# Mainboard.net
KiCad netlist of a schematic drawn in EAGLE
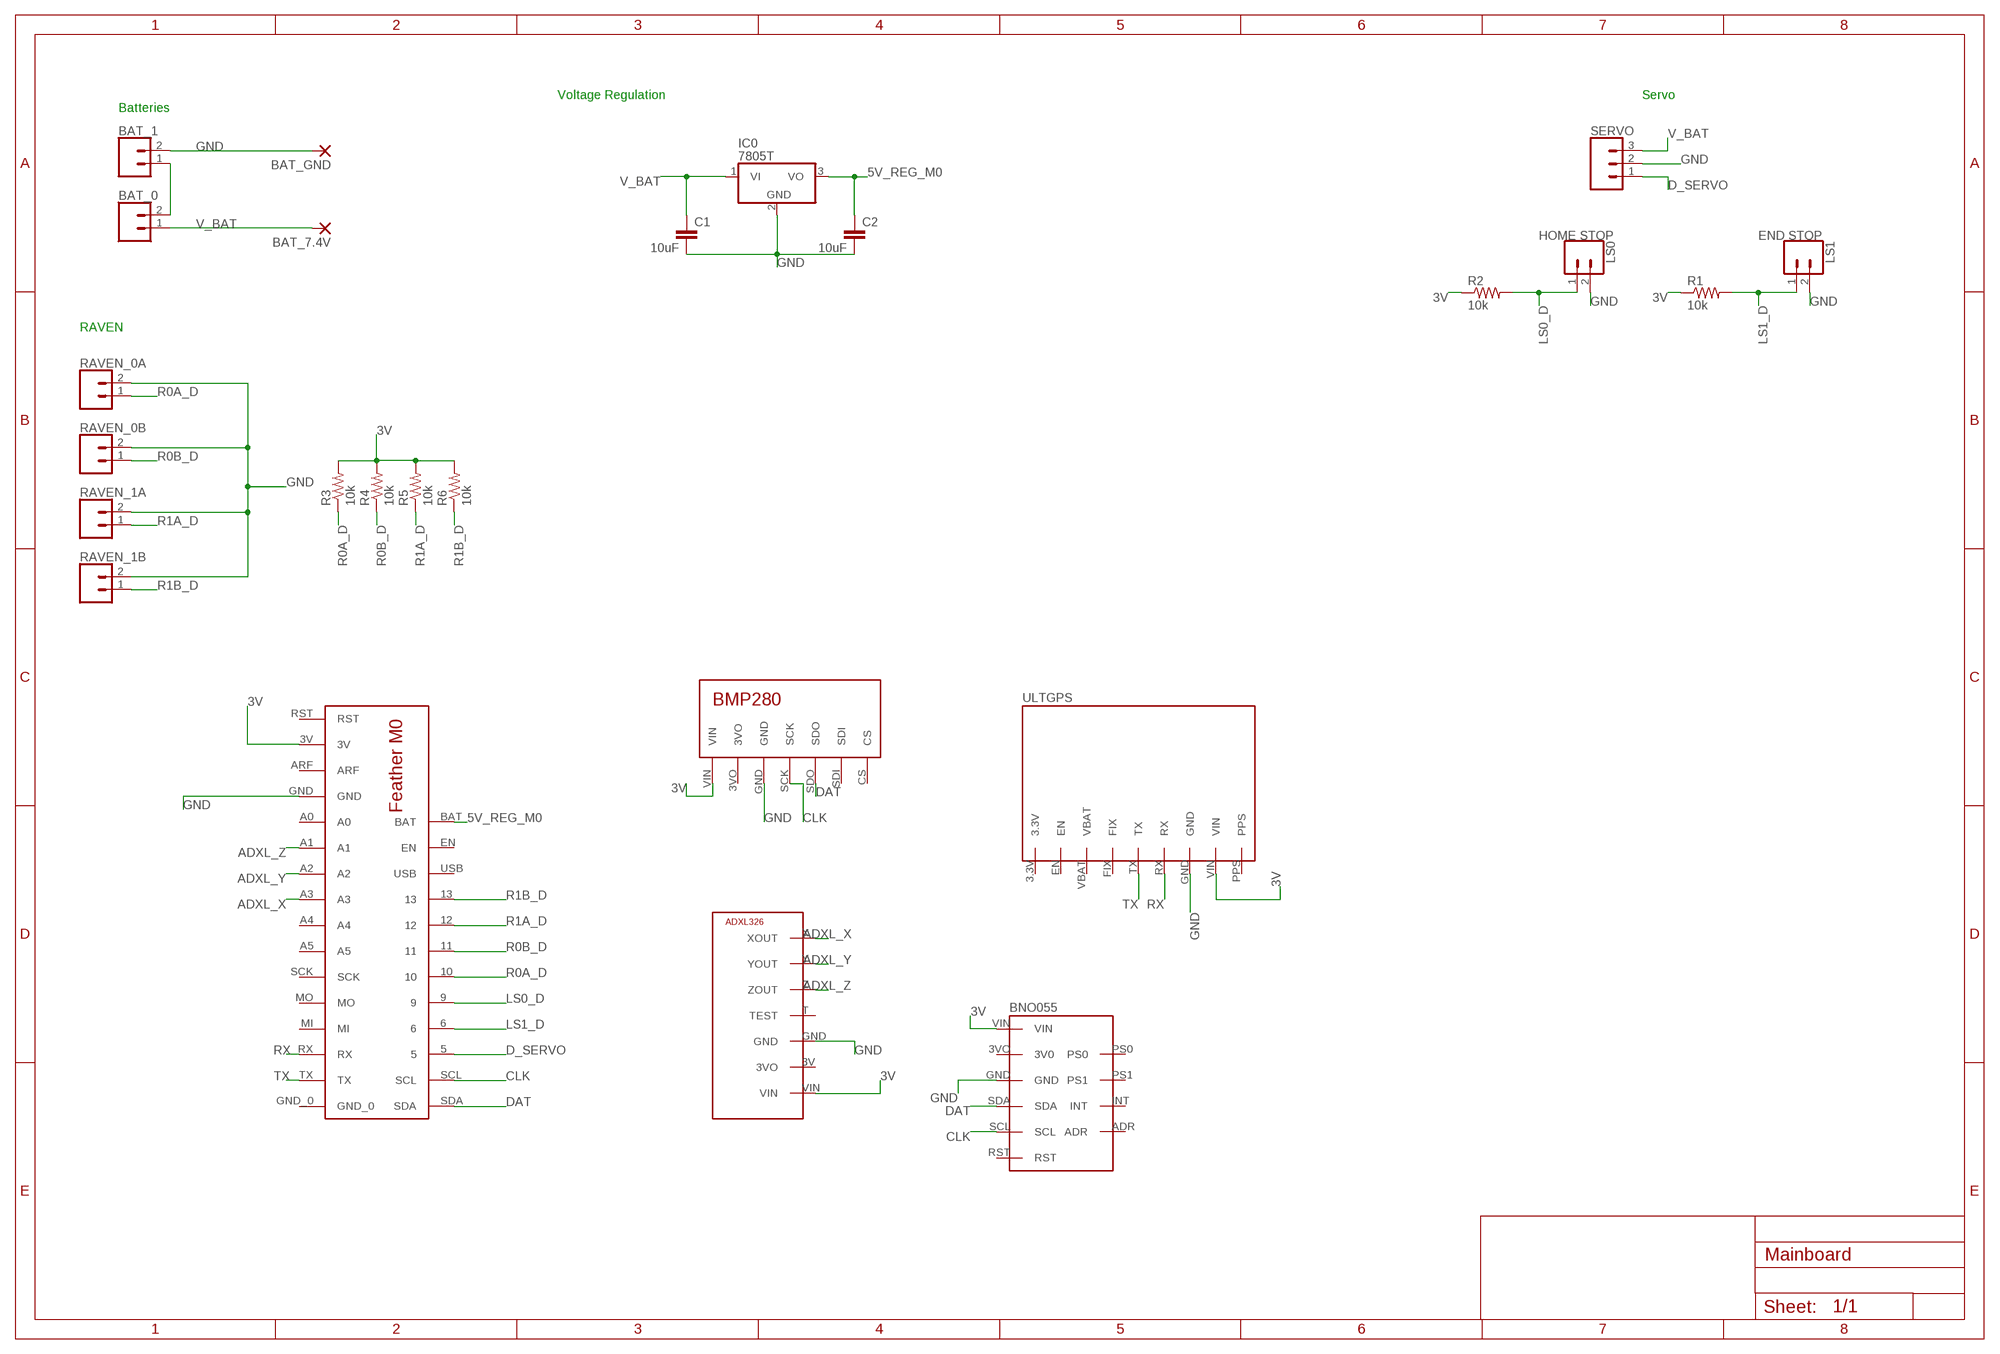
[diagram p0: schematic, sheet 1]

(export (version "E")
  (design (tool "Eeschema 10.0.6"))
  (components
    (comp (ref "BAT_0")
      (value "CONN_02JST-PTH-2")
      (footprint "eagle-import:JST-2-PTH")
      (libsource (lib "eagle-import") (part "CONN_02JST-PTH-2"))
    )
    (comp (ref "BAT_1")
      (value "CONN_02JST-PTH-2")
      (footprint "eagle-import:JST-2-PTH")
      (libsource (lib "eagle-import") (part "CONN_02JST-PTH-2"))
    )
    (comp (ref "BAT_7.4V")
      (value "3,81/1,4")
      (footprint "eagle-import:3,81_1,4")
      (libsource (lib "eagle-import") (part "3,81/1,4"))
    )
    (comp (ref "BAT_GND")
      (value "3,81/1,4")
      (footprint "eagle-import:3,81_1,4")
      (libsource (lib "eagle-import") (part "3,81/1,4"))
    )
    (comp (ref "C1")
      (value "10uF")
      (footprint "eagle-import:C2.5-3")
      (libsource (lib "eagle-import") (part "C2,5-3"))
    )
    (comp (ref "C2")
      (value "10uF")
      (footprint "eagle-import:C2.5-3")
      (libsource (lib "eagle-import") (part "C2,5-3"))
    )
    (comp (ref "IC0")
      (value "7805T")
      (footprint "eagle-import:TO220H")
      (libsource (lib "eagle-import") (part "78T05"))
    )
    (comp (ref "LS0")
      (value "HOME STOP")
      (footprint "eagle-import:JST-2-PTH")
      (libsource (lib "eagle-import") (part "CONN_02JST-PTH-2"))
    )
    (comp (ref "LS1")
      (value "END STOP")
      (footprint "eagle-import:JST-2-PTH")
      (libsource (lib "eagle-import") (part "CONN_02JST-PTH-2"))
    )
    (comp (ref "R1")
      (value "10k")
      (footprint "eagle-import:0207_10")
      (libsource (lib "eagle-import") (part "R-US_0207/10"))
    )
    (comp (ref "R2")
      (value "10k")
      (footprint "eagle-import:0207_10")
      (libsource (lib "eagle-import") (part "R-US_0207/10"))
    )
    (comp (ref "R3")
      (value "10k")
      (footprint "eagle-import:0207_10")
      (libsource (lib "eagle-import") (part "R-US_0207/10"))
    )
    (comp (ref "R4")
      (value "10k")
      (footprint "eagle-import:0207_10")
      (libsource (lib "eagle-import") (part "R-US_0207/10"))
    )
    (comp (ref "R5")
      (value "10k")
      (footprint "eagle-import:0207_10")
      (libsource (lib "eagle-import") (part "R-US_0207/10"))
    )
    (comp (ref "R6")
      (value "10k")
      (footprint "eagle-import:0207_10")
      (libsource (lib "eagle-import") (part "R-US_0207/10"))
    )
    (comp (ref "RAVEN_0A")
      (value "CONN_02JST-PTH-2")
      (footprint "eagle-import:JST-2-PTH")
      (libsource (lib "eagle-import") (part "CONN_02JST-PTH-2"))
    )
    (comp (ref "RAVEN_0B")
      (value "CONN_02JST-PTH-2")
      (footprint "eagle-import:JST-2-PTH")
      (libsource (lib "eagle-import") (part "CONN_02JST-PTH-2"))
    )
    (comp (ref "RAVEN_1A")
      (value "CONN_02JST-PTH-2")
      (footprint "eagle-import:JST-2-PTH")
      (libsource (lib "eagle-import") (part "CONN_02JST-PTH-2"))
    )
    (comp (ref "RAVEN_1B")
      (value "CONN_02JST-PTH-2")
      (footprint "eagle-import:JST-2-PTH")
      (libsource (lib "eagle-import") (part "CONN_02JST-PTH-2"))
    )
    (comp (ref "SERVO")
      (value "CONN_03JST-PTH")
      (footprint "eagle-import:JST-3-PTH")
      (libsource (lib "eagle-import") (part "CONN_03JST-PTH"))
    )
    (comp (ref "U$1") (value "M0") (footprint "eagle-import:M0") (libsource (lib "eagle-import") (part "M0")))
    (comp (ref "U$2")
      (value "BMP")
      (footprint "eagle-import:BMP")
      (libsource (lib "eagle-import") (part "BMP"))
    )
    (comp (ref "U$3")
      (value "ADXL377")
      (footprint "eagle-import:ADXL377")
      (libsource (lib "eagle-import") (part "ADXL377"))
    )
    (comp (ref "U$4")
      (value "ULTGPS")
      (footprint "eagle-import:ULTGPS")
      (libsource (lib "eagle-import") (part "ULTGPS"))
    )
    (comp (ref "U$5")
      (value "BNO055")
      (footprint "eagle-import:BNO055")
      (libsource (lib "eagle-import") (part "BNO055"))
    )
  )
  (nets
    (net (code "1") (name "/3V") (class "Default")
      (node (ref "R1") (pin "1") (pinfunction "1_1") (pintype "passive"))
      (node (ref "R2") (pin "1") (pinfunction "1_1") (pintype "passive"))
      (node (ref "R3") (pin "2") (pinfunction "2_2") (pintype "passive"))
      (node (ref "R4") (pin "2") (pinfunction "2_2") (pintype "passive"))
      (node (ref "R5") (pin "2") (pinfunction "2_2") (pintype "passive"))
      (node (ref "R6") (pin "2") (pinfunction "2_2") (pintype "passive"))
      (node (ref "U$1") (pin "3V") (pinfunction "3V_3V") (pintype "bidirectional"))
      (node (ref "U$2") (pin "VIN") (pinfunction "VIN_VIN") (pintype "bidirectional"))
      (node (ref "U$3") (pin "VIN") (pinfunction "VIN_VIN") (pintype "bidirectional"))
      (node (ref "U$4") (pin "VIN") (pinfunction "VIN_VIN") (pintype "input"))
      (node (ref "U$5") (pin "VIN") (pinfunction "VIN_VIN") (pintype "bidirectional"))
    )
    (net (code "2") (name "/5V_REG_M0") (class "Default")
      (node (ref "C2") (pin "1") (pinfunction "1_1") (pintype "passive"))
      (node (ref "IC0") (pin "3") (pinfunction "VO_3") (pintype "passive"))
      (node (ref "U$1") (pin "BAT") (pinfunction "BAT_BAT") (pintype "bidirectional"))
    )
    (net (code "3") (name "/ADXL_X") (class "Default")
      (node (ref "U$1") (pin "A3") (pinfunction "A3_A3") (pintype "bidirectional"))
      (node (ref "U$3") (pin "X") (pinfunction "XOUT_X") (pintype "bidirectional"))
    )
    (net (code "4") (name "/ADXL_Y") (class "Default")
      (node (ref "U$1") (pin "A2") (pinfunction "A2_A2") (pintype "bidirectional"))
      (node (ref "U$3") (pin "Y") (pinfunction "YOUT_Y") (pintype "bidirectional"))
    )
    (net (code "5") (name "/ADXL_Z") (class "Default")
      (node (ref "U$1") (pin "A1") (pinfunction "A1_A1") (pintype "bidirectional"))
      (node (ref "U$3") (pin "Z") (pinfunction "ZOUT_Z") (pintype "bidirectional"))
    )
    (net (code "6") (name "/CLK") (class "Default")
      (node (ref "U$1") (pin "SCL") (pinfunction "SCL_SCL") (pintype "bidirectional"))
      (node (ref "U$2") (pin "SCK") (pinfunction "SCK_SCK") (pintype "bidirectional"))
      (node (ref "U$5") (pin "SCL") (pinfunction "SCL_SCL") (pintype "bidirectional"))
    )
    (net (code "7") (name "/DAT") (class "Default")
      (node (ref "U$1") (pin "SDA") (pinfunction "SDA_SDA") (pintype "bidirectional"))
      (node (ref "U$2") (pin "SDO") (pinfunction "SDO_SDO") (pintype "bidirectional"))
      (node (ref "U$5") (pin "SDA") (pinfunction "SDA_SDA") (pintype "bidirectional"))
    )
    (net (code "8") (name "/D_SERVO") (class "Default")
      (node (ref "SERVO") (pin "1") (pinfunction "1_1") (pintype "passive"))
      (node (ref "U$1") (pin "5") (pinfunction "5_5") (pintype "bidirectional"))
    )
    (net (code "9") (name "/GND") (class "Default")
      (node (ref "BAT_1") (pin "2") (pinfunction "2_2") (pintype "passive"))
      (node (ref "BAT_GND") (pin "1") (pinfunction "P_1") (pintype "passive"))
      (node (ref "C1") (pin "2") (pinfunction "2_2") (pintype "passive"))
      (node (ref "C2") (pin "2") (pinfunction "2_2") (pintype "passive"))
      (node (ref "IC0") (pin "2") (pinfunction "GND_2") (pintype "passive"))
      (node (ref "LS0") (pin "2") (pinfunction "2_2") (pintype "passive"))
      (node (ref "LS1") (pin "2") (pinfunction "2_2") (pintype "passive"))
      (node (ref "RAVEN_0A") (pin "2") (pinfunction "2_2") (pintype "passive"))
      (node (ref "RAVEN_0B") (pin "2") (pinfunction "2_2") (pintype "passive"))
      (node (ref "RAVEN_1A") (pin "2") (pinfunction "2_2") (pintype "passive"))
      (node (ref "RAVEN_1B") (pin "2") (pinfunction "2_2") (pintype "passive"))
      (node (ref "SERVO") (pin "2") (pinfunction "2_2") (pintype "passive"))
      (node (ref "U$1") (pin "GND") (pinfunction "GND_GND") (pintype "bidirectional"))
      (node (ref "U$2") (pin "GND") (pinfunction "GND_GND") (pintype "bidirectional"))
      (node (ref "U$3") (pin "GND") (pinfunction "GND_GND") (pintype "bidirectional"))
      (node (ref "U$4") (pin "GND") (pinfunction "GND_GND") (pintype "power_in"))
      (node (ref "U$5") (pin "GND") (pinfunction "GND_GND") (pintype "bidirectional"))
    )
    (net (code "10") (name "/LS0_D") (class "Default")
      (node (ref "LS0") (pin "1") (pinfunction "1_1") (pintype "passive"))
      (node (ref "R2") (pin "2") (pinfunction "2_2") (pintype "passive"))
      (node (ref "U$1") (pin "9") (pinfunction "9_9") (pintype "bidirectional"))
    )
    (net (code "11") (name "/LS1_D") (class "Default")
      (node (ref "LS1") (pin "1") (pinfunction "1_1") (pintype "passive"))
      (node (ref "R1") (pin "2") (pinfunction "2_2") (pintype "passive"))
      (node (ref "U$1") (pin "6") (pinfunction "6_6") (pintype "bidirectional"))
    )
    (net (code "12") (name "/R0A_D") (class "Default")
      (node (ref "R3") (pin "1") (pinfunction "1_1") (pintype "passive"))
      (node (ref "RAVEN_0A") (pin "1") (pinfunction "1_1") (pintype "passive"))
      (node (ref "U$1") (pin "10") (pinfunction "10_10") (pintype "bidirectional"))
    )
    (net (code "13") (name "/R0B_D") (class "Default")
      (node (ref "R4") (pin "1") (pinfunction "1_1") (pintype "passive"))
      (node (ref "RAVEN_0B") (pin "1") (pinfunction "1_1") (pintype "passive"))
      (node (ref "U$1") (pin "11") (pinfunction "11_11") (pintype "bidirectional"))
    )
    (net (code "14") (name "/R1A_D") (class "Default")
      (node (ref "R5") (pin "1") (pinfunction "1_1") (pintype "passive"))
      (node (ref "RAVEN_1A") (pin "1") (pinfunction "1_1") (pintype "passive"))
      (node (ref "U$1") (pin "12") (pinfunction "12_12") (pintype "bidirectional"))
    )
    (net (code "15") (name "/R1B_D") (class "Default")
      (node (ref "R6") (pin "1") (pinfunction "1_1") (pintype "passive"))
      (node (ref "RAVEN_1B") (pin "1") (pinfunction "1_1") (pintype "passive"))
      (node (ref "U$1") (pin "13") (pinfunction "13_13") (pintype "bidirectional"))
    )
    (net (code "16") (name "/RX") (class "Default")
      (node (ref "U$1") (pin "RX") (pinfunction "RX_RX") (pintype "bidirectional"))
      (node (ref "U$4") (pin "RX") (pinfunction "RX_RX") (pintype "input"))
    )
    (net (code "17") (name "/TX") (class "Default")
      (node (ref "U$1") (pin "TX") (pinfunction "TX_TX") (pintype "bidirectional"))
      (node (ref "U$4") (pin "TX") (pinfunction "TX_TX") (pintype "output"))
    )
    (net (code "18") (name "/V_BAT") (class "Default")
      (node (ref "BAT_0") (pin "1") (pinfunction "1_1") (pintype "passive"))
      (node (ref "BAT_7.4V") (pin "1") (pinfunction "P_1") (pintype "passive"))
      (node (ref "C1") (pin "1") (pinfunction "1_1") (pintype "passive"))
      (node (ref "IC0") (pin "1") (pinfunction "VI_1") (pintype "input"))
      (node (ref "SERVO") (pin "3") (pinfunction "3_3") (pintype "passive"))
    )
    (net (code "19") (name "Net-(BAT_0-Pad2)") (class "Default")
      (node (ref "BAT_0") (pin "2") (pinfunction "2_2") (pintype "passive"))
      (node (ref "BAT_1") (pin "1") (pinfunction "1_1") (pintype "passive"))
    )
    (net (code "20") (name "unconnected-(U$1-PadA0)") (class "Default")
      (node (ref "U$1") (pin "A0") (pinfunction "A0_A0") (pintype "bidirectional"))
    )
    (net (code "21") (name "unconnected-(U$1-PadA4)") (class "Default")
      (node (ref "U$1") (pin "A4") (pinfunction "A4_A4") (pintype "bidirectional"))
    )
    (net (code "22") (name "unconnected-(U$1-PadA5)") (class "Default")
      (node (ref "U$1") (pin "A5") (pinfunction "A5_A5") (pintype "bidirectional"))
    )
    (net (code "23") (name "unconnected-(U$1-PadARF)") (class "Default")
      (node (ref "U$1") (pin "ARF") (pinfunction "ARF_ARF") (pintype "bidirectional"))
    )
    (net (code "24") (name "unconnected-(U$1-PadEN)") (class "Default")
      (node (ref "U$1") (pin "EN") (pinfunction "EN_EN") (pintype "bidirectional"))
    )
    (net (code "25") (name "unconnected-(U$1-PadGND_0)") (class "Default")
      (node (ref "U$1") (pin "GND_0") (pinfunction "GND_0_GND_0") (pintype "bidirectional"))
    )
    (net (code "26") (name "unconnected-(U$1-PadMI)") (class "Default")
      (node (ref "U$1") (pin "MI") (pinfunction "MI_MI") (pintype "bidirectional"))
    )
    (net (code "27") (name "unconnected-(U$1-PadMO)") (class "Default")
      (node (ref "U$1") (pin "MO") (pinfunction "MO_MO") (pintype "bidirectional"))
    )
    (net (code "28") (name "unconnected-(U$1-PadRST)") (class "Default")
      (node (ref "U$1") (pin "RST") (pinfunction "RST_RST") (pintype "bidirectional"))
    )
    (net (code "29") (name "unconnected-(U$1-PadSCK)") (class "Default")
      (node (ref "U$1") (pin "SCK") (pinfunction "SCK_SCK") (pintype "bidirectional"))
    )
    (net (code "30") (name "unconnected-(U$1-PadUSB)") (class "Default")
      (node (ref "U$1") (pin "USB") (pinfunction "USB_USB") (pintype "bidirectional"))
    )
    (net (code "31") (name "unconnected-(U$2-Pad3VO)") (class "Default")
      (node (ref "U$2") (pin "3VO") (pinfunction "3VO_3VO") (pintype "bidirectional"))
    )
    (net (code "32") (name "unconnected-(U$2-PadCS)") (class "Default")
      (node (ref "U$2") (pin "CS") (pinfunction "CS_CS") (pintype "bidirectional"))
    )
    (net (code "33") (name "unconnected-(U$2-PadSDI)") (class "Default")
      (node (ref "U$2") (pin "SDI") (pinfunction "SDI_SDI") (pintype "bidirectional"))
    )
    (net (code "34") (name "unconnected-(U$3-3VO-Pad3V)") (class "Default")
      (node (ref "U$3") (pin "3V") (pinfunction "3VO_3V") (pintype "bidirectional"))
    )
    (net (code "35") (name "unconnected-(U$3-TEST-PadT)") (class "Default")
      (node (ref "U$3") (pin "T") (pinfunction "TEST_T") (pintype "bidirectional"))
    )
    (net (code "36") (name "unconnected-(U$4-Pad3.3V)") (class "Default")
      (node (ref "U$4") (pin "3.3V") (pinfunction "3.3V_3.3V") (pintype "output"))
    )
    (net (code "37") (name "unconnected-(U$4-PadEN)") (class "Default")
      (node (ref "U$4") (pin "EN") (pinfunction "EN_EN") (pintype "input"))
    )
    (net (code "38") (name "unconnected-(U$4-PadFIX)") (class "Default")
      (node (ref "U$4") (pin "FIX") (pinfunction "FIX_FIX") (pintype "output"))
    )
    (net (code "39") (name "unconnected-(U$4-PadPPS)") (class "Default")
      (node (ref "U$4") (pin "PPS") (pinfunction "PPS_PPS") (pintype "output"))
    )
    (net (code "40") (name "unconnected-(U$4-PadVBAT)") (class "Default")
      (node (ref "U$4") (pin "VBAT") (pinfunction "VBAT_VBAT") (pintype "input"))
    )
    (net (code "41") (name "unconnected-(U$5-3V0-Pad3VO)") (class "Default")
      (node (ref "U$5") (pin "3VO") (pinfunction "3V0_3VO") (pintype "bidirectional"))
    )
    (net (code "42") (name "unconnected-(U$5-PadADR)") (class "Default")
      (node (ref "U$5") (pin "ADR") (pinfunction "ADR_ADR") (pintype "bidirectional"))
    )
    (net (code "43") (name "unconnected-(U$5-PadINT)") (class "Default")
      (node (ref "U$5") (pin "INT") (pinfunction "INT_INT") (pintype "bidirectional"))
    )
    (net (code "44") (name "unconnected-(U$5-PadPS0)") (class "Default")
      (node (ref "U$5") (pin "PS0") (pinfunction "PS0_PS0") (pintype "bidirectional"))
    )
    (net (code "45") (name "unconnected-(U$5-PadPS1)") (class "Default")
      (node (ref "U$5") (pin "PS1") (pinfunction "PS1_PS1") (pintype "bidirectional"))
    )
    (net (code "46") (name "unconnected-(U$5-PadRST)") (class "Default")
      (node (ref "U$5") (pin "RST") (pinfunction "RST_RST") (pintype "bidirectional"))
    )
  )
)
